# 02_DC-DCConverter.net
KiCad netlist of a schematic drawn in Altium Designer
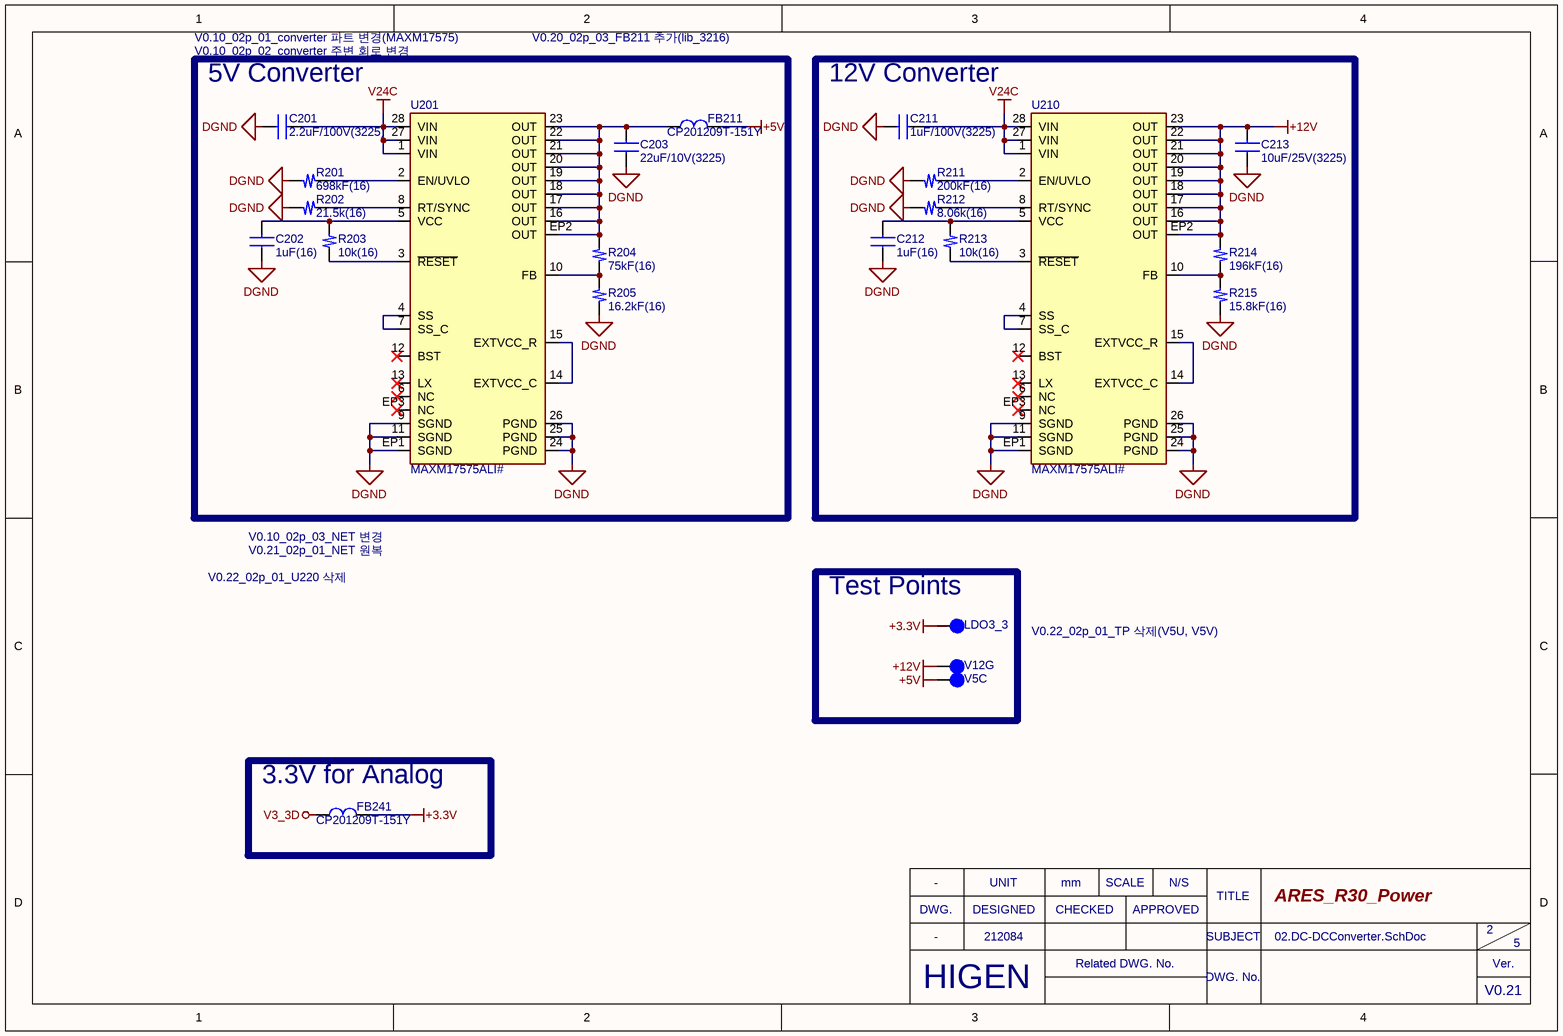
[diagram p0: 02.DC-DCConverter.SchDoc]

(export (version "E")
  (design (tool "Eeschema 10.0.6"))
  (components
    (comp (ref "C201")
      (value "2.2uF/100V(3225)")
      (footprint "C-3225")
      (libsource (lib "HIGEN") (part "Cap_NP"))
    )
    (comp (ref "C202") (value "1uF(16)") (footprint "C-1608S") (libsource (lib "HIGEN") (part "Cap_NP")))
    (comp (ref "C203")
      (value "22uF/10V(3225)")
      (footprint "C-3225")
      (libsource (lib "HIGEN") (part "Cap_NP"))
    )
    (comp (ref "C211")
      (value "1uF/100V(3225)")
      (footprint "C-3225")
      (libsource (lib "HIGEN") (part "Cap_NP"))
    )
    (comp (ref "C212") (value "1uF(16)") (footprint "C-1608S") (libsource (lib "HIGEN") (part "Cap_NP")))
    (comp (ref "C213")
      (value "10uF/25V(3225)")
      (footprint "C-3225")
      (libsource (lib "HIGEN") (part "Cap_NP"))
    )
    (comp (ref "FB211")
      (value "CP201209T-151Y")
      (footprint "L-2012")
      (libsource (lib "AM437X_MAIN_LOW") (part "FBead"))
    )
    (comp (ref "FB241")
      (value "CP201209T-151Y")
      (footprint "L-2012")
      (libsource (lib "AM437X_MAIN_LOW") (part "FBead"))
    )
    (comp (ref "LDO3_3")
      (value "TP")
      (footprint "TP-SMD")
      (fields (field (name "MFR") "Keystone Electronics") (field (name "TIINTPARTNUMBER") "2H0026"))
      (libsource (lib "*") (part "2H_TestPointThroughHole"))
    )
    (comp (ref "R201") (value "698kF(16)") (footprint "R-1608S") (libsource (lib "HIGEN") (part "Res")))
    (comp (ref "R202") (value "21.5k(16)") (footprint "R-1608S") (libsource (lib "HIGEN") (part "Res")))
    (comp (ref "R203") (value "10k(16)") (footprint "R-1608S") (libsource (lib "HIGEN") (part "Res")))
    (comp (ref "R204") (value "75kF(16)") (footprint "R-1608S") (libsource (lib "HIGEN") (part "Res")))
    (comp (ref "R205") (value "16.2kF(16)") (footprint "R-1608S") (libsource (lib "HIGEN") (part "Res")))
    (comp (ref "R211") (value "200kF(16)") (footprint "R-1608S") (libsource (lib "HIGEN") (part "Res")))
    (comp (ref "R212") (value "8.06k(16)") (footprint "R-1608S") (libsource (lib "HIGEN") (part "Res")))
    (comp (ref "R213") (value "10k(16)") (footprint "R-1608S") (libsource (lib "HIGEN") (part "Res")))
    (comp (ref "R214") (value "196kF(16)") (footprint "R-1608S") (libsource (lib "HIGEN") (part "Res")))
    (comp (ref "R215") (value "15.8kF(16)") (footprint "R-1608S") (libsource (lib "HIGEN") (part "Res")))
    (comp (ref "U201")
      (value "MAXM17575ALI#")
      (footprint "LGA28-0.5MM-10X6.5_3.45")
      (libsource (lib "HIGEN") (part "MAXM17575ALI#"))
    )
    (comp (ref "U210")
      (value "MAXM17575ALI#")
      (footprint "LGA28-0.5MM-10X6.5_3.45")
      (libsource (lib "HIGEN") (part "MAXM17575ALI#"))
    )
    (comp (ref "V5C")
      (value "TP")
      (footprint "TP-SMD")
      (fields (field (name "MFR") "Keystone Electronics") (field (name "TIINTPARTNUMBER") "2H0026"))
      (libsource (lib "*") (part "2H_TestPointThroughHole"))
    )
    (comp (ref "V12G")
      (value "TP")
      (footprint "TP-SMD")
      (fields (field (name "MFR") "Keystone Electronics") (field (name "TIINTPARTNUMBER") "2H0026"))
      (libsource (lib "*") (part "2H_TestPointThroughHole"))
    )
  )
  (nets
    (net (code "1") (name "+3.3V") (class "Default")
      (node (ref "FB241") (pin "2") (pinfunction "2_2") (pintype "passive"))
      (node (ref "LDO3_3") (pin "1") (pinfunction "1_1") (pintype "passive"))
    )
    (net (code "2") (name "+5V") (class "Default")
      (node (ref "FB211") (pin "2") (pinfunction "2_2") (pintype "passive"))
      (node (ref "V5C") (pin "1") (pinfunction "1_1") (pintype "passive"))
    )
    (net (code "3") (name "+12V") (class "Default")
      (node (ref "C213") (pin "2") (pinfunction "2_2") (pintype "passive"))
      (node (ref "R214") (pin "1") (pinfunction "P1_1") (pintype "passive"))
      (node (ref "U210") (pin "16") (pinfunction "OUT_16") (pintype "passive"))
      (node (ref "U210") (pin "17") (pinfunction "OUT_17") (pintype "passive"))
      (node (ref "U210") (pin "18") (pinfunction "OUT_18") (pintype "passive"))
      (node (ref "U210") (pin "19") (pinfunction "OUT_19") (pintype "passive"))
      (node (ref "U210") (pin "20") (pinfunction "OUT_20") (pintype "passive"))
      (node (ref "U210") (pin "21") (pinfunction "OUT_21") (pintype "passive"))
      (node (ref "U210") (pin "22") (pinfunction "OUT_22") (pintype "passive"))
      (node (ref "U210") (pin "23") (pinfunction "OUT_23") (pintype "passive"))
      (node (ref "U210") (pin "EP2") (pinfunction "OUT_EP2") (pintype "passive"))
      (node (ref "V12G") (pin "1") (pinfunction "1_1") (pintype "passive"))
    )
    (net (code "4") (name "DGND") (class "Default")
      (node (ref "C201") (pin "1") (pinfunction "1_1") (pintype "passive"))
      (node (ref "C202") (pin "2") (pinfunction "2_2") (pintype "passive"))
      (node (ref "C203") (pin "1") (pinfunction "1_1") (pintype "passive"))
      (node (ref "C211") (pin "1") (pinfunction "1_1") (pintype "passive"))
      (node (ref "C212") (pin "2") (pinfunction "2_2") (pintype "passive"))
      (node (ref "C213") (pin "1") (pinfunction "1_1") (pintype "passive"))
      (node (ref "R201") (pin "2") (pinfunction "P2_2") (pintype "passive"))
      (node (ref "R202") (pin "2") (pinfunction "P2_2") (pintype "passive"))
      (node (ref "R205") (pin "2") (pinfunction "P2_2") (pintype "passive"))
      (node (ref "R211") (pin "2") (pinfunction "P2_2") (pintype "passive"))
      (node (ref "R212") (pin "2") (pinfunction "P2_2") (pintype "passive"))
      (node (ref "R215") (pin "2") (pinfunction "P2_2") (pintype "passive"))
      (node (ref "U201") (pin "11") (pinfunction "SGND_11") (pintype "passive"))
      (node (ref "U201") (pin "24") (pinfunction "PGND_24") (pintype "passive"))
      (node (ref "U201") (pin "25") (pinfunction "PGND_25") (pintype "passive"))
      (node (ref "U201") (pin "26") (pinfunction "PGND_26") (pintype "passive"))
      (node (ref "U201") (pin "9") (pinfunction "SGND_9") (pintype "passive"))
      (node (ref "U201") (pin "EP1") (pinfunction "SGND_EP1") (pintype "passive"))
      (node (ref "U210") (pin "11") (pinfunction "SGND_11") (pintype "passive"))
      (node (ref "U210") (pin "24") (pinfunction "PGND_24") (pintype "passive"))
      (node (ref "U210") (pin "25") (pinfunction "PGND_25") (pintype "passive"))
      (node (ref "U210") (pin "26") (pinfunction "PGND_26") (pintype "passive"))
      (node (ref "U210") (pin "9") (pinfunction "SGND_9") (pintype "passive"))
      (node (ref "U210") (pin "EP1") (pinfunction "SGND_EP1") (pintype "passive"))
    )
    (net (code "5") (name "Net-(R201-P1)") (class "Default")
      (node (ref "R201") (pin "1") (pinfunction "P1_1") (pintype "passive"))
      (node (ref "U201") (pin "2") (pinfunction "EN/UVLO_2") (pintype "passive"))
    )
    (net (code "6") (name "Net-(R202-P1)") (class "Default")
      (node (ref "R202") (pin "1") (pinfunction "P1_1") (pintype "passive"))
      (node (ref "U201") (pin "8") (pinfunction "RT/SYNC_8") (pintype "passive"))
    )
    (net (code "7") (name "Net-(R203-P1)") (class "Default")
      (node (ref "C202") (pin "1") (pinfunction "1_1") (pintype "passive"))
      (node (ref "R203") (pin "1") (pinfunction "P1_1") (pintype "passive"))
      (node (ref "U201") (pin "5") (pinfunction "VCC_5") (pintype "passive"))
    )
    (net (code "8") (name "Net-(R203-P2)") (class "Default")
      (node (ref "R203") (pin "2") (pinfunction "P2_2") (pintype "passive"))
      (node (ref "U201") (pin "3") (pinfunction "~{RESET}_3") (pintype "passive"))
    )
    (net (code "9") (name "Net-(R204-P1)") (class "Default")
      (node (ref "C203") (pin "2") (pinfunction "2_2") (pintype "passive"))
      (node (ref "FB211") (pin "1") (pinfunction "1_1") (pintype "passive"))
      (node (ref "R204") (pin "1") (pinfunction "P1_1") (pintype "passive"))
      (node (ref "U201") (pin "16") (pinfunction "OUT_16") (pintype "passive"))
      (node (ref "U201") (pin "17") (pinfunction "OUT_17") (pintype "passive"))
      (node (ref "U201") (pin "18") (pinfunction "OUT_18") (pintype "passive"))
      (node (ref "U201") (pin "19") (pinfunction "OUT_19") (pintype "passive"))
      (node (ref "U201") (pin "20") (pinfunction "OUT_20") (pintype "passive"))
      (node (ref "U201") (pin "21") (pinfunction "OUT_21") (pintype "passive"))
      (node (ref "U201") (pin "22") (pinfunction "OUT_22") (pintype "passive"))
      (node (ref "U201") (pin "23") (pinfunction "OUT_23") (pintype "passive"))
      (node (ref "U201") (pin "EP2") (pinfunction "OUT_EP2") (pintype "passive"))
    )
    (net (code "10") (name "Net-(R204-P2)") (class "Default")
      (node (ref "R204") (pin "2") (pinfunction "P2_2") (pintype "passive"))
      (node (ref "R205") (pin "1") (pinfunction "P1_1") (pintype "passive"))
      (node (ref "U201") (pin "10") (pinfunction "FB_10") (pintype "passive"))
    )
    (net (code "11") (name "Net-(R211-P1)") (class "Default")
      (node (ref "R211") (pin "1") (pinfunction "P1_1") (pintype "passive"))
      (node (ref "U210") (pin "2") (pinfunction "EN/UVLO_2") (pintype "passive"))
    )
    (net (code "12") (name "Net-(R212-P1)") (class "Default")
      (node (ref "R212") (pin "1") (pinfunction "P1_1") (pintype "passive"))
      (node (ref "U210") (pin "8") (pinfunction "RT/SYNC_8") (pintype "passive"))
    )
    (net (code "13") (name "Net-(R213-P1)") (class "Default")
      (node (ref "C212") (pin "1") (pinfunction "1_1") (pintype "passive"))
      (node (ref "R213") (pin "1") (pinfunction "P1_1") (pintype "passive"))
      (node (ref "U210") (pin "5") (pinfunction "VCC_5") (pintype "passive"))
    )
    (net (code "14") (name "Net-(R213-P2)") (class "Default")
      (node (ref "R213") (pin "2") (pinfunction "P2_2") (pintype "passive"))
      (node (ref "U210") (pin "3") (pinfunction "~{RESET}_3") (pintype "passive"))
    )
    (net (code "15") (name "Net-(R214-P2)") (class "Default")
      (node (ref "R214") (pin "2") (pinfunction "P2_2") (pintype "passive"))
      (node (ref "R215") (pin "1") (pinfunction "P1_1") (pintype "passive"))
      (node (ref "U210") (pin "10") (pinfunction "FB_10") (pintype "passive"))
    )
    (net (code "16") (name "Net-(U201-EXTVCC_C)") (class "Default")
      (node (ref "U201") (pin "14") (pinfunction "EXTVCC_C_14") (pintype "passive"))
      (node (ref "U201") (pin "15") (pinfunction "EXTVCC_R_15") (pintype "passive"))
    )
    (net (code "17") (name "Net-(U201-SS)") (class "Default")
      (node (ref "U201") (pin "4") (pinfunction "SS_4") (pintype "passive"))
      (node (ref "U201") (pin "7") (pinfunction "SS_C_7") (pintype "passive"))
    )
    (net (code "18") (name "Net-(U210-EXTVCC_C)") (class "Default")
      (node (ref "U210") (pin "14") (pinfunction "EXTVCC_C_14") (pintype "passive"))
      (node (ref "U210") (pin "15") (pinfunction "EXTVCC_R_15") (pintype "passive"))
    )
    (net (code "19") (name "Net-(U210-SS)") (class "Default")
      (node (ref "U210") (pin "4") (pinfunction "SS_4") (pintype "passive"))
      (node (ref "U210") (pin "7") (pinfunction "SS_C_7") (pintype "passive"))
    )
    (net (code "20") (name "V3_3D") (class "Default")
      (node (ref "FB241") (pin "1") (pinfunction "1_1") (pintype "passive"))
    )
    (net (code "21") (name "V24C") (class "Default")
      (node (ref "C201") (pin "2") (pinfunction "2_2") (pintype "passive"))
      (node (ref "C211") (pin "2") (pinfunction "2_2") (pintype "passive"))
      (node (ref "U201") (pin "1") (pinfunction "VIN_1") (pintype "passive"))
      (node (ref "U201") (pin "27") (pinfunction "VIN_27") (pintype "passive"))
      (node (ref "U201") (pin "28") (pinfunction "VIN_28") (pintype "passive"))
      (node (ref "U210") (pin "1") (pinfunction "VIN_1") (pintype "passive"))
      (node (ref "U210") (pin "27") (pinfunction "VIN_27") (pintype "passive"))
      (node (ref "U210") (pin "28") (pinfunction "VIN_28") (pintype "passive"))
    )
    (net (code "22") (name "unconnected-(U201-BST-Pad12)") (class "Default")
      (node (ref "U201") (pin "12") (pinfunction "BST_12") (pintype "passive+no_connect"))
    )
    (net (code "23") (name "unconnected-(U201-LX-Pad13)") (class "Default")
      (node (ref "U201") (pin "13") (pinfunction "LX_13") (pintype "passive+no_connect"))
    )
    (net (code "24") (name "unconnected-(U201-NC-Pad6)") (class "Default")
      (node (ref "U201") (pin "6") (pinfunction "NC_6") (pintype "passive+no_connect"))
    )
    (net (code "25") (name "unconnected-(U201-NC-PadEP3)") (class "Default")
      (node (ref "U201") (pin "EP3") (pinfunction "NC_EP3") (pintype "passive+no_connect"))
    )
    (net (code "26") (name "unconnected-(U210-BST-Pad12)") (class "Default")
      (node (ref "U210") (pin "12") (pinfunction "BST_12") (pintype "passive+no_connect"))
    )
    (net (code "27") (name "unconnected-(U210-LX-Pad13)") (class "Default")
      (node (ref "U210") (pin "13") (pinfunction "LX_13") (pintype "passive+no_connect"))
    )
    (net (code "28") (name "unconnected-(U210-NC-Pad6)") (class "Default")
      (node (ref "U210") (pin "6") (pinfunction "NC_6") (pintype "passive+no_connect"))
    )
    (net (code "29") (name "unconnected-(U210-NC-PadEP3)") (class "Default")
      (node (ref "U210") (pin "EP3") (pinfunction "NC_EP3") (pintype "passive+no_connect"))
    )
  )
)
